# main.net
KiCad netlist of a schematic drawn in Altium Designer
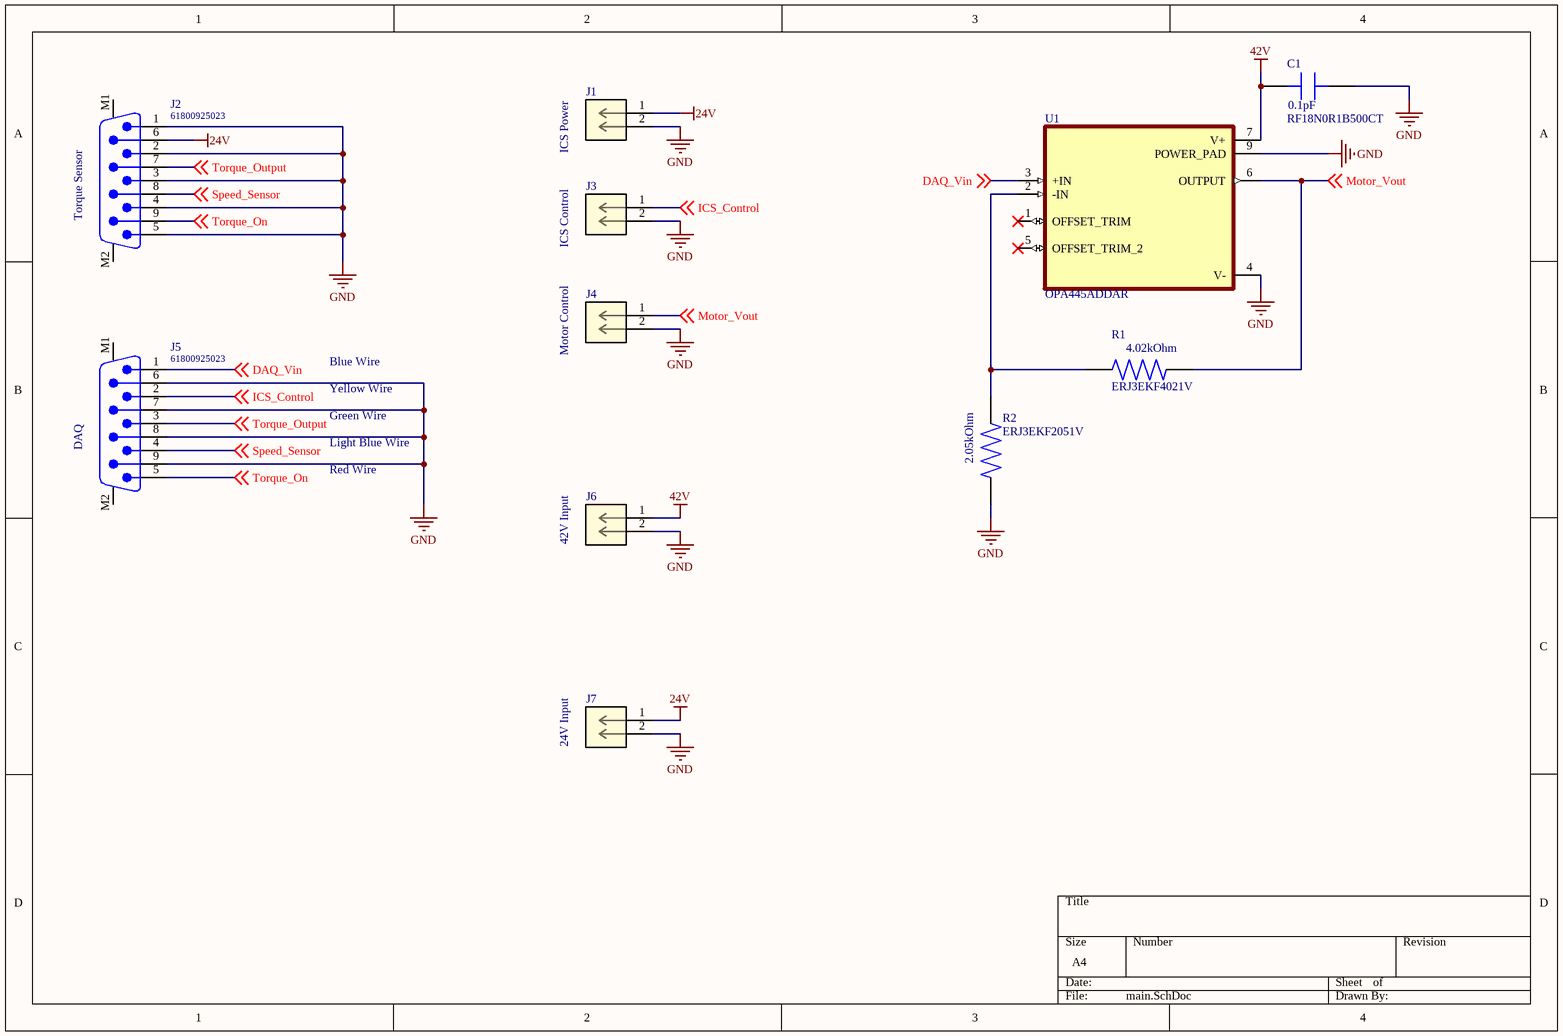
[diagram p0: main.SchDoc]

(export (version "E")
  (design (tool "Eeschema 10.0.6"))
  (components
    (comp (ref "C1")
      (value "RF18N0R1B500CT")
      (footprint "0603")
      (libsource (lib "Control_Board") (part "RF18N0R1B500CT"))
    )
    (comp (ref "J1")
      (value "https://www.digikey.ca/en/products/detail/molex/0731375003/1465136")
      (footprint "CONN_73137-5003_MOL")
      (fields
        (field (name "MANUFACTURER_PART_NUMBER") "731375003")
        (field (name "COPYRIGHT") "Copyright (C) 2022 Ultra Librarian. All rights reserved.")
      )
      (libsource (lib "Control_Board") (part "731375003"))
    )
    (comp (ref "J2")
      (value "61800925023")
      (footprint "61800925023")
      (description "Male PCB Connector WR-DSUB, Vertical, 9 pins")
      (fields (field (name "MANUFACTURER") "Wurth Elektronik") (field (name "PUBLISHER") "WurthElektronik"))
      (libsource (lib "Altium Content Vault") (part "WE-CN-2S-2M-D9"))
    )
    (comp (ref "J3")
      (value "https://www.digikey.ca/en/products/detail/molex/0731375003/1465136")
      (footprint "CONN_73137-5003_MOL")
      (fields
        (field (name "MANUFACTURER_PART_NUMBER") "731375003")
        (field (name "COPYRIGHT") "Copyright (C) 2022 Ultra Librarian. All rights reserved.")
      )
      (libsource (lib "Control_Board") (part "731375003"))
    )
    (comp (ref "J4")
      (value "https://www.digikey.ca/en/products/detail/molex/0731375003/1465136")
      (footprint "CONN_73137-5003_MOL")
      (fields
        (field (name "MANUFACTURER_PART_NUMBER") "731375003")
        (field (name "COPYRIGHT") "Copyright (C) 2022 Ultra Librarian. All rights reserved.")
      )
      (libsource (lib "Control_Board") (part "731375003"))
    )
    (comp (ref "J5")
      (value "61800925023")
      (footprint "61800925023")
      (description "Male PCB Connector WR-DSUB, Vertical, 9 pins")
      (fields (field (name "MANUFACTURER") "Wurth Elektronik") (field (name "PUBLISHER") "WurthElektronik"))
      (libsource (lib "Altium Content Vault") (part "WE-CN-2S-2M-D9"))
    )
    (comp (ref "J6")
      (value "https://www.digikey.ca/en/products/detail/molex/0731375003/1465136")
      (footprint "CONN_73137-5003_MOL")
      (fields
        (field (name "MANUFACTURER_PART_NUMBER") "731375003")
        (field (name "COPYRIGHT") "Copyright (C) 2022 Ultra Librarian. All rights reserved.")
      )
      (libsource (lib "Control_Board") (part "731375003"))
    )
    (comp (ref "J7")
      (value "https://www.digikey.ca/en/products/detail/molex/0731375003/1465136")
      (footprint "CONN_73137-5003_MOL")
      (fields
        (field (name "MANUFACTURER_PART_NUMBER") "731375003")
        (field (name "COPYRIGHT") "Copyright (C) 2022 Ultra Librarian. All rights reserved.")
      )
      (libsource (lib "Control_Board") (part "731375003"))
    )
    (comp (ref "R1")
      (value "ERJ3EKF4021V")
      (footprint "0603")
      (libsource (lib "Control_Board") (part "ERJ3EKF4021V"))
    )
    (comp (ref "R2")
      (value "ERJ3EKF2051V")
      (footprint "0603")
      (libsource (lib "Control_Board") (part "ERJ3EKF2051V"))
    )
    (comp (ref "U1")
      (value "OPA445ADDAR")
      (footprint "VREG_LM5017MR/NOPB")
      (libsource (lib "Control_Board") (part "OPA445ADDAR"))
    )
  )
  (nets
    (net (code "1") (name "24V") (class "Default")
      (node (ref "J1") (pin "1") (pinfunction "1_1") (pintype "passive"))
      (node (ref "J2") (pin "6") (pinfunction "6_6") (pintype "passive"))
      (node (ref "J7") (pin "1") (pinfunction "1_1") (pintype "passive"))
    )
    (net (code "2") (name "42V") (class "Default")
      (node (ref "C1") (pin "1") (pinfunction "1_1") (pintype "passive"))
      (node (ref "J6") (pin "1") (pinfunction "1_1") (pintype "passive"))
      (node (ref "U1") (pin "7") (pinfunction "V+_7") (pintype "power_in"))
    )
    (net (code "3") (name "DAQ_Vin") (class "Default")
      (node (ref "J5") (pin "1") (pinfunction "1_1") (pintype "passive"))
      (node (ref "U1") (pin "3") (pinfunction "+IN_3") (pintype "input"))
    )
    (net (code "4") (name "GND") (class "Default")
      (node (ref "C1") (pin "2") (pinfunction "2_2") (pintype "passive"))
      (node (ref "J1") (pin "2") (pinfunction "2_2") (pintype "passive"))
      (node (ref "J2") (pin "1") (pinfunction "1_1") (pintype "passive"))
      (node (ref "J2") (pin "2") (pinfunction "2_2") (pintype "passive"))
      (node (ref "J2") (pin "3") (pinfunction "3_3") (pintype "passive"))
      (node (ref "J2") (pin "4") (pinfunction "4_4") (pintype "passive"))
      (node (ref "J2") (pin "5") (pinfunction "5_5") (pintype "passive"))
      (node (ref "J3") (pin "2") (pinfunction "2_2") (pintype "passive"))
      (node (ref "J4") (pin "2") (pinfunction "2_2") (pintype "passive"))
      (node (ref "J5") (pin "6") (pinfunction "6_6") (pintype "passive"))
      (node (ref "J5") (pin "7") (pinfunction "7_7") (pintype "passive"))
      (node (ref "J5") (pin "8") (pinfunction "8_8") (pintype "passive"))
      (node (ref "J5") (pin "9") (pinfunction "9_9") (pintype "passive"))
      (node (ref "J6") (pin "2") (pinfunction "2_2") (pintype "passive"))
      (node (ref "J7") (pin "2") (pinfunction "2_2") (pintype "passive"))
      (node (ref "R2") (pin "1") (pinfunction "1_1") (pintype "passive"))
      (node (ref "U1") (pin "4") (pinfunction "V-_4") (pintype "power_in"))
      (node (ref "U1") (pin "9") (pinfunction "POWER_PAD_9") (pintype "power_in"))
    )
    (net (code "5") (name "ICS_Control") (class "Default")
      (node (ref "J3") (pin "1") (pinfunction "1_1") (pintype "passive"))
      (node (ref "J5") (pin "2") (pinfunction "2_2") (pintype "passive"))
    )
    (net (code "6") (name "Motor_Vout") (class "Default")
      (node (ref "J4") (pin "1") (pinfunction "1_1") (pintype "passive"))
      (node (ref "R1") (pin "2") (pinfunction "2_2") (pintype "passive"))
      (node (ref "U1") (pin "6") (pinfunction "OUTPUT_6") (pintype "output"))
    )
    (net (code "7") (name "Net-(U1--IN)") (class "Default")
      (node (ref "R1") (pin "1") (pinfunction "1_1") (pintype "passive"))
      (node (ref "R2") (pin "2") (pinfunction "2_2") (pintype "passive"))
      (node (ref "U1") (pin "2") (pinfunction "-IN_2") (pintype "input"))
    )
    (net (code "8") (name "Speed_Sensor") (class "Default")
      (node (ref "J2") (pin "8") (pinfunction "8_8") (pintype "passive"))
      (node (ref "J5") (pin "4") (pinfunction "4_4") (pintype "passive"))
    )
    (net (code "9") (name "Torque_On") (class "Default")
      (node (ref "J2") (pin "9") (pinfunction "9_9") (pintype "passive"))
      (node (ref "J5") (pin "5") (pinfunction "5_5") (pintype "passive"))
    )
    (net (code "10") (name "Torque_Output") (class "Default")
      (node (ref "J2") (pin "7") (pinfunction "7_7") (pintype "passive"))
      (node (ref "J5") (pin "3") (pinfunction "3_3") (pintype "passive"))
    )
    (net (code "11") (name "unconnected-(J2-PadM1)") (class "Default")
      (node (ref "J2") (pin "M1") (pinfunction "M1_M1") (pintype "passive"))
    )
    (net (code "12") (name "unconnected-(J2-PadM2)") (class "Default")
      (node (ref "J2") (pin "M2") (pinfunction "M2_M2") (pintype "passive"))
    )
    (net (code "13") (name "unconnected-(J5-PadM1)") (class "Default")
      (node (ref "J5") (pin "M1") (pinfunction "M1_M1") (pintype "passive"))
    )
    (net (code "14") (name "unconnected-(J5-PadM2)") (class "Default")
      (node (ref "J5") (pin "M2") (pinfunction "M2_M2") (pintype "passive"))
    )
    (net (code "15") (name "unconnected-(U1-OFFSET_TRIM-Pad1)") (class "Default")
      (node (ref "U1") (pin "1") (pinfunction "OFFSET_TRIM_1") (pintype "bidirectional+no_connect"))
    )
    (net (code "16") (name "unconnected-(U1-OFFSET_TRIM_2-Pad5)") (class "Default")
      (node (ref "U1") (pin "5") (pinfunction "OFFSET_TRIM_2_5") (pintype "bidirectional+no_connect"))
    )
  )
)
